# Power.net
KiCad netlist of a schematic drawn in Altium Designer
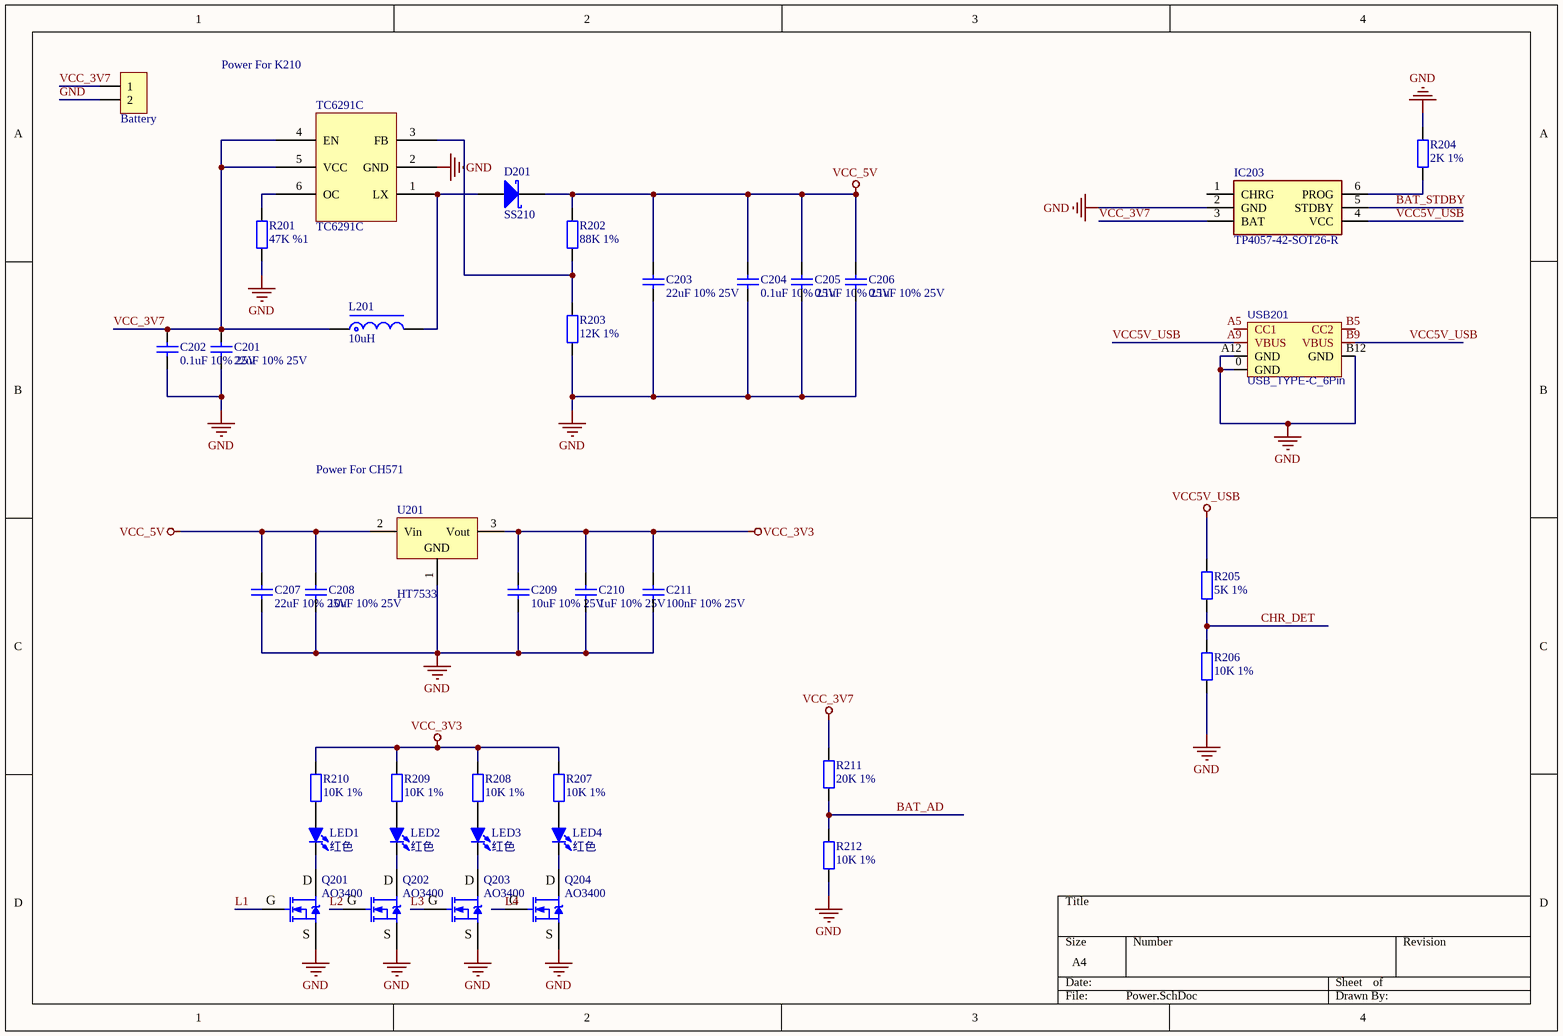
[diagram p0: Power.SchDoc]

(export (version "E")
  (design (tool "Eeschema 10.0.6"))
  (components
    (comp (ref "Battery")
      (value "HDR-1X2")
      (footprint "ZH1.5-LI-2P")
      (description "2P接插件")
      (libsource (lib "5.3 - 1.50mm连接器(ZH1.5)") (part "Header 2"))
    )
    (comp (ref "C201")
      (value "22uF 10% 25V")
      (footprint "C1206_L")
      (description "贴片电容/MLCC电容")
      (libsource (lib "0.1 - 电阻-电容-电感-晶振-晶体-磁珠-电位器-法拉电容-馈通电容") (part "C"))
    )
    (comp (ref "C202")
      (value "0.1uF 10% 25V")
      (footprint "C0603_L")
      (description "贴片电容/MLCC电容")
      (libsource (lib "0.1 - 电阻-电容-电感-晶振-晶体-磁珠-电位器-法拉电容-馈通电容") (part "C"))
    )
    (comp (ref "C203")
      (value "22uF 10% 25V")
      (footprint "C1206_L")
      (description "贴片电容/MLCC电容")
      (libsource (lib "0.1 - 电阻-电容-电感-晶振-晶体-磁珠-电位器-法拉电容-馈通电容") (part "C"))
    )
    (comp (ref "C204")
      (value "0.1uF 10% 25V")
      (footprint "C0603_L")
      (description "贴片电容/MLCC电容")
      (libsource (lib "0.1 - 电阻-电容-电感-晶振-晶体-磁珠-电位器-法拉电容-馈通电容") (part "C"))
    )
    (comp (ref "C205")
      (value "0.1uF 10% 25V")
      (footprint "C0603_L")
      (description "贴片电容/MLCC电容")
      (libsource (lib "0.1 - 电阻-电容-电感-晶振-晶体-磁珠-电位器-法拉电容-馈通电容") (part "C"))
    )
    (comp (ref "C206")
      (value "0.1uF 10% 25V")
      (footprint "C0603_L")
      (description "贴片电容/MLCC电容")
      (libsource (lib "0.1 - 电阻-电容-电感-晶振-晶体-磁珠-电位器-法拉电容-馈通电容") (part "C"))
    )
    (comp (ref "C207")
      (value "22uF 10% 25V")
      (footprint "C1206_L")
      (description "贴片电容/MLCC电容")
      (libsource (lib "0.1 - 电阻-电容-电感-晶振-晶体-磁珠-电位器-法拉电容-馈通电容") (part "C"))
    )
    (comp (ref "C208")
      (value "10uF 10% 25V")
      (footprint "C0805_L")
      (description "贴片电容/MLCC电容")
      (libsource (lib "0.1 - 电阻-电容-电感-晶振-晶体-磁珠-电位器-法拉电容-馈通电容") (part "C"))
    )
    (comp (ref "C209")
      (value "10uF 10% 25V")
      (footprint "C0805_L")
      (description "贴片电容/MLCC电容")
      (libsource (lib "0.1 - 电阻-电容-电感-晶振-晶体-磁珠-电位器-法拉电容-馈通电容") (part "C"))
    )
    (comp (ref "C210")
      (value "1uF 10% 25V")
      (footprint "C0805_L")
      (description "贴片电容/MLCC电容")
      (libsource (lib "0.1 - 电阻-电容-电感-晶振-晶体-磁珠-电位器-法拉电容-馈通电容") (part "C"))
    )
    (comp (ref "C211")
      (value "100nF 10% 25V")
      (footprint "C0805_L")
      (description "贴片电容/MLCC电容")
      (libsource (lib "0.1 - 电阻-电容-电感-晶振-晶体-磁珠-电位器-法拉电容-馈通电容") (part "C"))
    )
    (comp (ref "D201")
      (value "SS210")
      (footprint "SMA")
      (description "肖特基二极管")
      (libsource (lib "0.2 - 二极管-TVS-ESD-整流桥-放电管") (part "SS210"))
    )
    (comp (ref "IC203")
      (value "TP4057-42-SOT26-R")
      (footprint "SamacSys:SOT95P280X125-6N")
      (description "Integrated Circuit")
      (libsource (lib "SamacSys") (part "TP4057-42-SOT26-R"))
    )
    (comp (ref "L201")
      (value "10uH")
      (footprint "CD52")
      (description "CD系列贴片线绕功率电感")
      (libsource (lib "0.1 - 电阻-电容-电感-晶振-晶体-磁珠-电位器-法拉电容-馈通电容") (part "L-SMD"))
    )
    (comp (ref "LED1")
      (value "红色")
      (footprint "LED0805_G")
      (description "贴片LED")
      (libsource (lib "0.3 - LED发光二极管-IR二极管_接收管-光耦") (part "LED-SMD"))
    )
    (comp (ref "LED2")
      (value "红色")
      (footprint "LED0805_G")
      (description "贴片LED")
      (libsource (lib "0.3 - LED发光二极管-IR二极管_接收管-光耦") (part "LED-SMD"))
    )
    (comp (ref "LED3")
      (value "红色")
      (footprint "LED0805_G")
      (description "贴片LED")
      (libsource (lib "0.3 - LED发光二极管-IR二极管_接收管-光耦") (part "LED-SMD"))
    )
    (comp (ref "LED4")
      (value "红色")
      (footprint "LED0805_G")
      (description "贴片LED")
      (libsource (lib "0.3 - LED发光二极管-IR二极管_接收管-光耦") (part "LED-SMD"))
    )
    (comp (ref "Q201")
      (value "AO3400")
      (footprint "SOT23-3N")
      (description "N沟道 30V/4.2A")
      (libsource (lib "0.4 - 三极管-场效应管-可控硅") (part "AO3400"))
    )
    (comp (ref "Q202")
      (value "AO3400")
      (footprint "SOT23-3N")
      (description "N沟道 30V/4.2A")
      (libsource (lib "0.4 - 三极管-场效应管-可控硅") (part "AO3400"))
    )
    (comp (ref "Q203")
      (value "AO3400")
      (footprint "SOT23-3N")
      (description "N沟道 30V/4.2A")
      (libsource (lib "0.4 - 三极管-场效应管-可控硅") (part "AO3400"))
    )
    (comp (ref "Q204")
      (value "AO3400")
      (footprint "SOT23-3N")
      (description "N沟道 30V/4.2A")
      (libsource (lib "0.4 - 三极管-场效应管-可控硅") (part "AO3400"))
    )
    (comp (ref "R201")
      (value "47K %1")
      (footprint "R0603_L")
      (description "贴片电阻")
      (libsource (lib "0.1 - 电阻-电容-电感-晶振-晶体-磁珠-电位器-法拉电容-馈通电容") (part "R"))
    )
    (comp (ref "R202")
      (value "88K 1%")
      (footprint "R0603_L")
      (description "贴片电阻")
      (libsource (lib "0.1 - 电阻-电容-电感-晶振-晶体-磁珠-电位器-法拉电容-馈通电容") (part "R"))
    )
    (comp (ref "R203")
      (value "12K 1%")
      (footprint "R0603_L")
      (description "贴片电阻")
      (libsource (lib "0.1 - 电阻-电容-电感-晶振-晶体-磁珠-电位器-法拉电容-馈通电容") (part "R"))
    )
    (comp (ref "R204")
      (value "2K 1%")
      (footprint "R0603_L")
      (description "贴片电阻")
      (libsource (lib "0.1 - 电阻-电容-电感-晶振-晶体-磁珠-电位器-法拉电容-馈通电容") (part "R"))
    )
    (comp (ref "R205")
      (value "5K 1%")
      (footprint "R0603_L")
      (description "贴片电阻")
      (libsource (lib "0.1 - 电阻-电容-电感-晶振-晶体-磁珠-电位器-法拉电容-馈通电容") (part "R"))
    )
    (comp (ref "R206")
      (value "10K 1%")
      (footprint "R0603_L")
      (description "贴片电阻")
      (libsource (lib "0.1 - 电阻-电容-电感-晶振-晶体-磁珠-电位器-法拉电容-馈通电容") (part "R"))
    )
    (comp (ref "R207")
      (value "10K 1%")
      (footprint "R0603_L")
      (description "贴片电阻")
      (libsource (lib "0.1 - 电阻-电容-电感-晶振-晶体-磁珠-电位器-法拉电容-馈通电容") (part "R"))
    )
    (comp (ref "R208")
      (value "10K 1%")
      (footprint "R0603_L")
      (description "贴片电阻")
      (libsource (lib "0.1 - 电阻-电容-电感-晶振-晶体-磁珠-电位器-法拉电容-馈通电容") (part "R"))
    )
    (comp (ref "R209")
      (value "10K 1%")
      (footprint "R0603_L")
      (description "贴片电阻")
      (libsource (lib "0.1 - 电阻-电容-电感-晶振-晶体-磁珠-电位器-法拉电容-馈通电容") (part "R"))
    )
    (comp (ref "R210")
      (value "10K 1%")
      (footprint "R0603_L")
      (description "贴片电阻")
      (libsource (lib "0.1 - 电阻-电容-电感-晶振-晶体-磁珠-电位器-法拉电容-馈通电容") (part "R"))
    )
    (comp (ref "R211")
      (value "20K 1%")
      (footprint "R0603_L")
      (description "贴片电阻")
      (libsource (lib "0.1 - 电阻-电容-电感-晶振-晶体-磁珠-电位器-法拉电容-馈通电容") (part "R"))
    )
    (comp (ref "R212")
      (value "10K 1%")
      (footprint "R0603_L")
      (description "贴片电阻")
      (libsource (lib "0.1 - 电阻-电容-电感-晶振-晶体-磁珠-电位器-法拉电容-馈通电容") (part "R"))
    )
    (comp (ref "TC6291C")
      (value "TC6291C")
      (footprint "SOT23-6")
      (libsource (lib "calorieScale") (part "TC6291C"))
    )
    (comp (ref "U201")
      (value "HT7533")
      (footprint "SOT89_N")
      (description "LDO线性稳压芯片")
      (libsource (lib "0.7 - 电源类芯片") (part "HT7533"))
    )
    (comp (ref "USB201")
      (value "USB_TYPE-C_6Pin")
      (footprint "USB-C-SMD_6P")
      (description "USB_TYPE-C_6Pin母座")
      (libsource (lib "0.6 - 电源_RJ45以太网_音频_SD-TF_SIM_ USB Type-C_HDMI插座") (part "USB_TYPE-C_6Pin"))
    )
  )
  (nets
    (net (code "1") (name "/BAT_AD") (class "Default")
      (node (ref "R211") (pin "1") (pinfunction "1_1") (pintype "passive"))
      (node (ref "R212") (pin "2") (pinfunction "2_2") (pintype "passive"))
    )
    (net (code "2") (name "/BAT_STDBY") (class "Default")
      (node (ref "IC203") (pin "5") (pinfunction "STDBY_5") (pintype "passive"))
    )
    (net (code "3") (name "/CHR_DET") (class "Default")
      (node (ref "R205") (pin "1") (pinfunction "1_1") (pintype "passive"))
      (node (ref "R206") (pin "2") (pinfunction "2_2") (pintype "passive"))
    )
    (net (code "4") (name "/L1") (class "Default")
      (node (ref "Q201") (pin "1") (pinfunction "G_1") (pintype "passive"))
    )
    (net (code "5") (name "/L2") (class "Default")
      (node (ref "Q202") (pin "1") (pinfunction "G_1") (pintype "passive"))
    )
    (net (code "6") (name "/L3") (class "Default")
      (node (ref "Q203") (pin "1") (pinfunction "G_1") (pintype "passive"))
    )
    (net (code "7") (name "/L4") (class "Default")
      (node (ref "Q204") (pin "1") (pinfunction "G_1") (pintype "passive"))
    )
    (net (code "8") (name "GND") (class "Default")
      (node (ref "Battery") (pin "2") (pinfunction "2_2") (pintype "passive"))
      (node (ref "C201") (pin "1") (pinfunction "1_1") (pintype "passive"))
      (node (ref "C202") (pin "1") (pinfunction "1_1") (pintype "passive"))
      (node (ref "C203") (pin "1") (pinfunction "1_1") (pintype "passive"))
      (node (ref "C204") (pin "1") (pinfunction "1_1") (pintype "passive"))
      (node (ref "C205") (pin "1") (pinfunction "1_1") (pintype "passive"))
      (node (ref "C206") (pin "1") (pinfunction "1_1") (pintype "passive"))
      (node (ref "C207") (pin "1") (pinfunction "1_1") (pintype "passive"))
      (node (ref "C208") (pin "1") (pinfunction "1_1") (pintype "passive"))
      (node (ref "C209") (pin "1") (pinfunction "1_1") (pintype "passive"))
      (node (ref "C210") (pin "1") (pinfunction "1_1") (pintype "passive"))
      (node (ref "C211") (pin "1") (pinfunction "1_1") (pintype "passive"))
      (node (ref "IC203") (pin "2") (pinfunction "GND_2") (pintype "passive"))
      (node (ref "Q201") (pin "2") (pinfunction "S_2") (pintype "passive"))
      (node (ref "Q202") (pin "2") (pinfunction "S_2") (pintype "passive"))
      (node (ref "Q203") (pin "2") (pinfunction "S_2") (pintype "passive"))
      (node (ref "Q204") (pin "2") (pinfunction "S_2") (pintype "passive"))
      (node (ref "R201") (pin "1") (pinfunction "1_1") (pintype "passive"))
      (node (ref "R203") (pin "1") (pinfunction "1_1") (pintype "passive"))
      (node (ref "R204") (pin "2") (pinfunction "2_2") (pintype "passive"))
      (node (ref "R206") (pin "1") (pinfunction "1_1") (pintype "passive"))
      (node (ref "R212") (pin "1") (pinfunction "1_1") (pintype "passive"))
      (node (ref "TC6291C") (pin "2") (pinfunction "GND_2") (pintype "passive"))
      (node (ref "U201") (pin "1") (pinfunction "GND_1") (pintype "passive"))
      (node (ref "USB201") (pin "0") (pinfunction "GND_0") (pintype "passive"))
      (node (ref "USB201") (pin "A12") (pinfunction "GND_A12") (pintype "passive"))
      (node (ref "USB201") (pin "B12") (pinfunction "GND_B12") (pintype "passive"))
    )
    (net (code "9") (name "Net-(D201-A)") (class "Default")
      (node (ref "D201") (pin "1") (pinfunction "A_1") (pintype "passive"))
      (node (ref "L201") (pin "2") (pinfunction "2_2") (pintype "passive"))
      (node (ref "TC6291C") (pin "1") (pinfunction "LX_1") (pintype "passive"))
    )
    (net (code "10") (name "Net-(IC203-PROG)") (class "Default")
      (node (ref "IC203") (pin "6") (pinfunction "PROG_6") (pintype "passive"))
      (node (ref "R204") (pin "1") (pinfunction "1_1") (pintype "passive"))
    )
    (net (code "11") (name "Net-(LED1-A)") (class "Default")
      (node (ref "LED1") (pin "1") (pinfunction "A_1") (pintype "passive"))
      (node (ref "R210") (pin "1") (pinfunction "1_1") (pintype "passive"))
    )
    (net (code "12") (name "Net-(LED1-K)") (class "Default")
      (node (ref "LED1") (pin "2") (pinfunction "K_2") (pintype "passive"))
      (node (ref "Q201") (pin "3") (pinfunction "D_3") (pintype "passive"))
    )
    (net (code "13") (name "Net-(LED2-A)") (class "Default")
      (node (ref "LED2") (pin "1") (pinfunction "A_1") (pintype "passive"))
      (node (ref "R209") (pin "1") (pinfunction "1_1") (pintype "passive"))
    )
    (net (code "14") (name "Net-(LED2-K)") (class "Default")
      (node (ref "LED2") (pin "2") (pinfunction "K_2") (pintype "passive"))
      (node (ref "Q202") (pin "3") (pinfunction "D_3") (pintype "passive"))
    )
    (net (code "15") (name "Net-(LED3-A)") (class "Default")
      (node (ref "LED3") (pin "1") (pinfunction "A_1") (pintype "passive"))
      (node (ref "R208") (pin "1") (pinfunction "1_1") (pintype "passive"))
    )
    (net (code "16") (name "Net-(LED3-K)") (class "Default")
      (node (ref "LED3") (pin "2") (pinfunction "K_2") (pintype "passive"))
      (node (ref "Q203") (pin "3") (pinfunction "D_3") (pintype "passive"))
    )
    (net (code "17") (name "Net-(LED4-A)") (class "Default")
      (node (ref "LED4") (pin "1") (pinfunction "A_1") (pintype "passive"))
      (node (ref "R207") (pin "1") (pinfunction "1_1") (pintype "passive"))
    )
    (net (code "18") (name "Net-(LED4-K)") (class "Default")
      (node (ref "LED4") (pin "2") (pinfunction "K_2") (pintype "passive"))
      (node (ref "Q204") (pin "3") (pinfunction "D_3") (pintype "passive"))
    )
    (net (code "19") (name "Net-(TC6291C-FB)") (class "Default")
      (node (ref "R202") (pin "1") (pinfunction "1_1") (pintype "passive"))
      (node (ref "R203") (pin "2") (pinfunction "2_2") (pintype "passive"))
      (node (ref "TC6291C") (pin "3") (pinfunction "FB_3") (pintype "passive"))
    )
    (net (code "20") (name "Net-(TC6291C-OC)") (class "Default")
      (node (ref "R201") (pin "2") (pinfunction "2_2") (pintype "passive"))
      (node (ref "TC6291C") (pin "6") (pinfunction "OC_6") (pintype "passive"))
    )
    (net (code "21") (name "VCC5V_USB") (class "Default")
      (node (ref "IC203") (pin "4") (pinfunction "VCC_4") (pintype "passive"))
      (node (ref "R205") (pin "2") (pinfunction "2_2") (pintype "passive"))
      (node (ref "USB201") (pin "A9") (pinfunction "VBUS_A9") (pintype "passive"))
      (node (ref "USB201") (pin "B9") (pinfunction "VBUS_B9") (pintype "passive"))
    )
    (net (code "22") (name "VCC_3V3") (class "Default")
      (node (ref "C209") (pin "2") (pinfunction "2_2") (pintype "passive"))
      (node (ref "C210") (pin "2") (pinfunction "2_2") (pintype "passive"))
      (node (ref "C211") (pin "2") (pinfunction "2_2") (pintype "passive"))
      (node (ref "R207") (pin "2") (pinfunction "2_2") (pintype "passive"))
      (node (ref "R208") (pin "2") (pinfunction "2_2") (pintype "passive"))
      (node (ref "R209") (pin "2") (pinfunction "2_2") (pintype "passive"))
      (node (ref "R210") (pin "2") (pinfunction "2_2") (pintype "passive"))
      (node (ref "U201") (pin "3") (pinfunction "Vout_3") (pintype "passive"))
    )
    (net (code "23") (name "VCC_3V7") (class "Default")
      (node (ref "Battery") (pin "1") (pinfunction "1_1") (pintype "passive"))
      (node (ref "C201") (pin "2") (pinfunction "2_2") (pintype "passive"))
      (node (ref "C202") (pin "2") (pinfunction "2_2") (pintype "passive"))
      (node (ref "IC203") (pin "3") (pinfunction "BAT_3") (pintype "passive"))
      (node (ref "L201") (pin "1") (pinfunction "1_1") (pintype "passive"))
      (node (ref "R211") (pin "2") (pinfunction "2_2") (pintype "passive"))
      (node (ref "TC6291C") (pin "4") (pinfunction "EN_4") (pintype "passive"))
      (node (ref "TC6291C") (pin "5") (pinfunction "VCC_5") (pintype "passive"))
    )
    (net (code "24") (name "VCC_5V") (class "Default")
      (node (ref "C203") (pin "2") (pinfunction "2_2") (pintype "passive"))
      (node (ref "C204") (pin "2") (pinfunction "2_2") (pintype "passive"))
      (node (ref "C205") (pin "2") (pinfunction "2_2") (pintype "passive"))
      (node (ref "C206") (pin "2") (pinfunction "2_2") (pintype "passive"))
      (node (ref "C207") (pin "2") (pinfunction "2_2") (pintype "passive"))
      (node (ref "C208") (pin "2") (pinfunction "2_2") (pintype "passive"))
      (node (ref "D201") (pin "2") (pinfunction "K_2") (pintype "passive"))
      (node (ref "R202") (pin "2") (pinfunction "2_2") (pintype "passive"))
      (node (ref "U201") (pin "2") (pinfunction "Vin_2") (pintype "passive"))
    )
    (net (code "25") (name "unconnected-(IC203-CHRG-Pad1)") (class "Default")
      (node (ref "IC203") (pin "1") (pinfunction "CHRG_1") (pintype "passive"))
    )
    (net (code "26") (name "unconnected-(USB201-CC1-PadA5)") (class "Default")
      (node (ref "USB201") (pin "A5") (pinfunction "CC1_A5") (pintype "passive"))
    )
    (net (code "27") (name "unconnected-(USB201-CC2-PadB5)") (class "Default")
      (node (ref "USB201") (pin "B5") (pinfunction "CC2_B5") (pintype "passive"))
    )
  )
)
